# design.net
KiCad netlist of a schematic drawn in Altium Designer
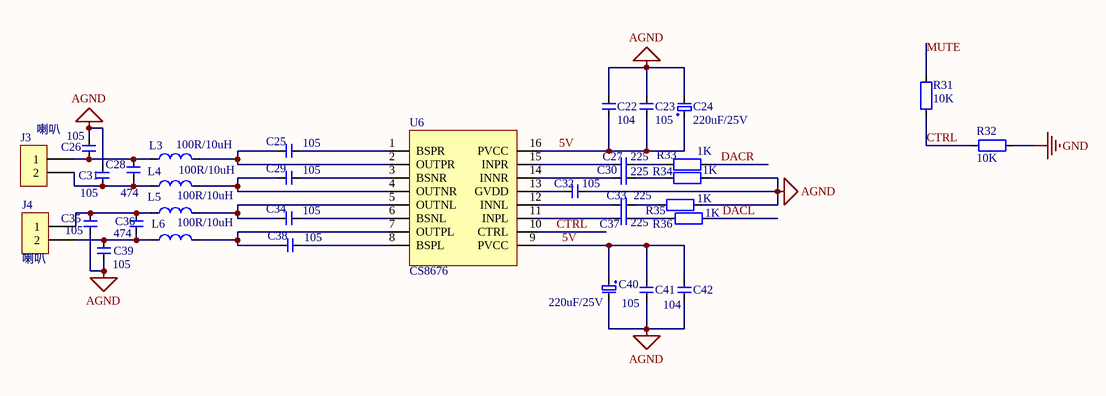
[diagram p0: 功放原理图.SchDoc]

(export (version "E")
  (design (tool "Eeschema 10.0.6"))
  (components
    (comp (ref "C22") (value "104") (footprint "C0603") (libsource (lib "MY") (part "CAP-0603")))
    (comp (ref "C23") (value "105") (footprint "C0603") (libsource (lib "MY") (part "CAP-0603")))
    (comp (ref "C24") (value "220uF/25V") (footprint "EC2.5-6.3") (libsource (lib "MY") (part "+CAP")))
    (comp (ref "C25") (value "105") (footprint "C0603") (libsource (lib "MY") (part "CAP-0603")))
    (comp (ref "C26") (value "105") (footprint "C0603") (libsource (lib "MY") (part "CAP-0603")))
    (comp (ref "C27") (value "225") (footprint "C0603") (libsource (lib "MY") (part "CAP-0603")))
    (comp (ref "C28") (value "474") (footprint "C0603") (libsource (lib "MY") (part "CAP-0603")))
    (comp (ref "C29") (value "105") (footprint "C0603") (libsource (lib "MY") (part "CAP-0603")))
    (comp (ref "C30") (value "225") (footprint "C0603") (libsource (lib "MY") (part "CAP-0603")))
    (comp (ref "C31") (value "105") (footprint "C0603") (libsource (lib "MY") (part "CAP-0603")))
    (comp (ref "C32") (value "105") (footprint "C0603") (libsource (lib "MY") (part "CAP-0603")))
    (comp (ref "C33") (value "225") (footprint "C0603") (libsource (lib "MY") (part "CAP-0603")))
    (comp (ref "C34") (value "105") (footprint "C0603") (libsource (lib "MY") (part "CAP-0603")))
    (comp (ref "C35") (value "105") (footprint "C0603") (libsource (lib "MY") (part "CAP-0603")))
    (comp (ref "C36") (value "474") (footprint "C0603") (libsource (lib "MY") (part "CAP-0603")))
    (comp (ref "C37") (value "225") (footprint "C0603") (libsource (lib "MY") (part "CAP-0603")))
    (comp (ref "C38") (value "105") (footprint "C0603") (libsource (lib "MY") (part "CAP-0603")))
    (comp (ref "C39") (value "105") (footprint "C0603") (libsource (lib "MY") (part "CAP-0603")))
    (comp (ref "C40") (value "220uF/25V") (footprint "EC2.5-6.3") (libsource (lib "MY") (part "+CAP")))
    (comp (ref "C41") (value "105") (footprint "C0603") (libsource (lib "MY") (part "CAP-0603")))
    (comp (ref "C42") (value "104") (footprint "C0603") (libsource (lib "MY") (part "CAP-0603")))
    (comp (ref "J3")
      (value "喇叭")
      (footprint "CON-2X2.54")
      (description "Connector")
      (libsource (lib "*") (part "CON2"))
    )
    (comp (ref "J4")
      (value "喇叭")
      (footprint "CON-2X2.54")
      (description "Connector")
      (libsource (lib "*") (part "CON2"))
    )
    (comp (ref "L3") (value "100R/10uH") (footprint "R1206") (libsource (lib "MY") (part "L")))
    (comp (ref "L4") (value "100R/10uH") (footprint "R1206") (libsource (lib "MY") (part "L")))
    (comp (ref "L5") (value "100R/10uH") (footprint "R1206") (libsource (lib "MY") (part "L")))
    (comp (ref "L6") (value "100R/10uH") (footprint "R1206") (libsource (lib "MY") (part "L")))
    (comp (ref "R31") (value "10K") (footprint "R0603") (libsource (lib "MY") (part "RES-0603")))
    (comp (ref "R32") (value "10K") (footprint "R0603") (libsource (lib "MY") (part "RES-0603")))
    (comp (ref "R33") (value "1K") (footprint "R0603") (libsource (lib "MY") (part "RES-0603")))
    (comp (ref "R34") (value "1K") (footprint "R0603") (libsource (lib "MY") (part "RES-0603")))
    (comp (ref "R35") (value "1K") (footprint "R0603") (libsource (lib "MY") (part "RES-0603")))
    (comp (ref "R36") (value "1K") (footprint "R0603") (libsource (lib "MY") (part "RES-0603")))
    (comp (ref "U6") (value "CS8676") (footprint "SOP16-EP") (libsource (lib "MY") (part "CS8676")))
  )
  (nets
    (net (code "1") (name "/5V") (class "Default")
      (node (ref "C22") (pin "1") (pinfunction "1_1") (pintype "passive"))
      (node (ref "C23") (pin "1") (pinfunction "1_1") (pintype "passive"))
      (node (ref "C24") (pin "1") (pinfunction "1_1") (pintype "passive"))
      (node (ref "C40") (pin "1") (pinfunction "1_1") (pintype "passive"))
      (node (ref "C41") (pin "1") (pinfunction "1_1") (pintype "passive"))
      (node (ref "C42") (pin "1") (pinfunction "1_1") (pintype "passive"))
      (node (ref "U6") (pin "16") (pinfunction "PVCC_16") (pintype "passive"))
      (node (ref "U6") (pin "9") (pinfunction "PVCC_9") (pintype "passive"))
    )
    (net (code "2") (name "/CTRL") (class "Default")
      (node (ref "R31") (pin "1") (pinfunction "1_1") (pintype "passive"))
      (node (ref "R32") (pin "1") (pinfunction "1_1") (pintype "passive"))
      (node (ref "U6") (pin "10") (pinfunction "CTRL_10") (pintype "passive"))
    )
    (net (code "3") (name "/DACL") (class "Default")
      (node (ref "R36") (pin "2") (pinfunction "2_2") (pintype "passive"))
    )
    (net (code "4") (name "/DACR") (class "Default")
      (node (ref "R33") (pin "2") (pinfunction "2_2") (pintype "passive"))
    )
    (net (code "5") (name "/MUTE") (class "Default")
      (node (ref "R31") (pin "2") (pinfunction "2_2") (pintype "passive"))
    )
    (net (code "6") (name "AGND") (class "Default")
      (node (ref "C22") (pin "2") (pinfunction "2_2") (pintype "passive"))
      (node (ref "C23") (pin "2") (pinfunction "2_2") (pintype "passive"))
      (node (ref "C24") (pin "2") (pinfunction "2_2") (pintype "passive"))
      (node (ref "C26") (pin "2") (pinfunction "2_2") (pintype "passive"))
      (node (ref "C31") (pin "2") (pinfunction "2_2") (pintype "passive"))
      (node (ref "C32") (pin "2") (pinfunction "2_2") (pintype "passive"))
      (node (ref "C35") (pin "2") (pinfunction "2_2") (pintype "passive"))
      (node (ref "C39") (pin "2") (pinfunction "2_2") (pintype "passive"))
      (node (ref "C40") (pin "2") (pinfunction "2_2") (pintype "passive"))
      (node (ref "C41") (pin "2") (pinfunction "2_2") (pintype "passive"))
      (node (ref "C42") (pin "2") (pinfunction "2_2") (pintype "passive"))
      (node (ref "R34") (pin "2") (pinfunction "2_2") (pintype "passive"))
      (node (ref "R35") (pin "2") (pinfunction "2_2") (pintype "passive"))
    )
    (net (code "7") (name "GND") (class "Default")
      (node (ref "R32") (pin "2") (pinfunction "2_2") (pintype "passive"))
    )
    (net (code "8") (name "Net-(C26-Pad1)") (class "Default")
      (node (ref "C26") (pin "1") (pinfunction "1_1") (pintype "passive"))
      (node (ref "C28") (pin "2") (pinfunction "2_2") (pintype "passive"))
      (node (ref "J3") (pin "1") (pinfunction "1_1") (pintype "passive"))
      (node (ref "L3") (pin "1") (pinfunction "1_1") (pintype "passive"))
    )
    (net (code "9") (name "Net-(C27-Pad2)") (class "Default")
      (node (ref "C27") (pin "2") (pinfunction "2_2") (pintype "passive"))
      (node (ref "R33") (pin "1") (pinfunction "1_1") (pintype "passive"))
    )
    (net (code "10") (name "Net-(C28-Pad1)") (class "Default")
      (node (ref "C28") (pin "1") (pinfunction "1_1") (pintype "passive"))
      (node (ref "C31") (pin "1") (pinfunction "1_1") (pintype "passive"))
      (node (ref "J3") (pin "2") (pinfunction "2_2") (pintype "passive"))
      (node (ref "L4") (pin "1") (pinfunction "1_1") (pintype "passive"))
    )
    (net (code "11") (name "Net-(C30-Pad2)") (class "Default")
      (node (ref "C30") (pin "2") (pinfunction "2_2") (pintype "passive"))
      (node (ref "R34") (pin "1") (pinfunction "1_1") (pintype "passive"))
    )
    (net (code "12") (name "Net-(C33-Pad2)") (class "Default")
      (node (ref "C33") (pin "2") (pinfunction "2_2") (pintype "passive"))
      (node (ref "R35") (pin "1") (pinfunction "1_1") (pintype "passive"))
    )
    (net (code "13") (name "Net-(C35-Pad1)") (class "Default")
      (node (ref "C35") (pin "1") (pinfunction "1_1") (pintype "passive"))
      (node (ref "C36") (pin "2") (pinfunction "2_2") (pintype "passive"))
      (node (ref "J4") (pin "1") (pinfunction "1_1") (pintype "passive"))
      (node (ref "L5") (pin "1") (pinfunction "1_1") (pintype "passive"))
    )
    (net (code "14") (name "Net-(C36-Pad1)") (class "Default")
      (node (ref "C36") (pin "1") (pinfunction "1_1") (pintype "passive"))
      (node (ref "C39") (pin "1") (pinfunction "1_1") (pintype "passive"))
      (node (ref "J4") (pin "2") (pinfunction "2_2") (pintype "passive"))
      (node (ref "L6") (pin "1") (pinfunction "1_1") (pintype "passive"))
    )
    (net (code "15") (name "Net-(C37-Pad2)") (class "Default")
      (node (ref "C37") (pin "2") (pinfunction "2_2") (pintype "passive"))
      (node (ref "R36") (pin "1") (pinfunction "1_1") (pintype "passive"))
    )
    (net (code "16") (name "Net-(U6-BSNL)") (class "Default")
      (node (ref "C34") (pin "2") (pinfunction "2_2") (pintype "passive"))
      (node (ref "U6") (pin "6") (pinfunction "BSNL_6") (pintype "passive"))
    )
    (net (code "17") (name "Net-(U6-BSNR)") (class "Default")
      (node (ref "C29") (pin "2") (pinfunction "2_2") (pintype "passive"))
      (node (ref "U6") (pin "3") (pinfunction "BSNR_3") (pintype "passive"))
    )
    (net (code "18") (name "Net-(U6-BSPL)") (class "Default")
      (node (ref "C38") (pin "2") (pinfunction "2_2") (pintype "passive"))
      (node (ref "U6") (pin "8") (pinfunction "BSPL_8") (pintype "passive"))
    )
    (net (code "19") (name "Net-(U6-BSPR)") (class "Default")
      (node (ref "C25") (pin "2") (pinfunction "2_2") (pintype "passive"))
      (node (ref "U6") (pin "1") (pinfunction "BSPR_1") (pintype "passive"))
    )
    (net (code "20") (name "Net-(U6-GVDD)") (class "Default")
      (node (ref "C32") (pin "1") (pinfunction "1_1") (pintype "passive"))
      (node (ref "U6") (pin "13") (pinfunction "GVDD_13") (pintype "passive"))
    )
    (net (code "21") (name "Net-(U6-INNL)") (class "Default")
      (node (ref "C33") (pin "1") (pinfunction "1_1") (pintype "passive"))
      (node (ref "U6") (pin "12") (pinfunction "INNL_12") (pintype "passive"))
    )
    (net (code "22") (name "Net-(U6-INNR)") (class "Default")
      (node (ref "C30") (pin "1") (pinfunction "1_1") (pintype "passive"))
      (node (ref "U6") (pin "14") (pinfunction "INNR_14") (pintype "passive"))
    )
    (net (code "23") (name "Net-(U6-INPL)") (class "Default")
      (node (ref "C37") (pin "1") (pinfunction "1_1") (pintype "passive"))
      (node (ref "U6") (pin "11") (pinfunction "INPL_11") (pintype "passive"))
    )
    (net (code "24") (name "Net-(U6-INPR)") (class "Default")
      (node (ref "C27") (pin "1") (pinfunction "1_1") (pintype "passive"))
      (node (ref "U6") (pin "15") (pinfunction "INPR_15") (pintype "passive"))
    )
    (net (code "25") (name "Net-(U6-OUTNL)") (class "Default")
      (node (ref "C34") (pin "1") (pinfunction "1_1") (pintype "passive"))
      (node (ref "L5") (pin "2") (pinfunction "2_2") (pintype "passive"))
      (node (ref "U6") (pin "5") (pinfunction "OUTNL_5") (pintype "passive"))
    )
    (net (code "26") (name "Net-(U6-OUTNR)") (class "Default")
      (node (ref "C29") (pin "1") (pinfunction "1_1") (pintype "passive"))
      (node (ref "L4") (pin "2") (pinfunction "2_2") (pintype "passive"))
      (node (ref "U6") (pin "4") (pinfunction "OUTNR_4") (pintype "passive"))
    )
    (net (code "27") (name "Net-(U6-OUTPL)") (class "Default")
      (node (ref "C38") (pin "1") (pinfunction "1_1") (pintype "passive"))
      (node (ref "L6") (pin "2") (pinfunction "2_2") (pintype "passive"))
      (node (ref "U6") (pin "7") (pinfunction "OUTPL_7") (pintype "passive"))
    )
    (net (code "28") (name "Net-(U6-OUTPR)") (class "Default")
      (node (ref "C25") (pin "1") (pinfunction "1_1") (pintype "passive"))
      (node (ref "L3") (pin "2") (pinfunction "2_2") (pintype "passive"))
      (node (ref "U6") (pin "2") (pinfunction "OUTPR_2") (pintype "passive"))
    )
  )
)
